# 6_uart_esc_i2c.net
KiCad netlist of a schematic drawn in Altium Designer
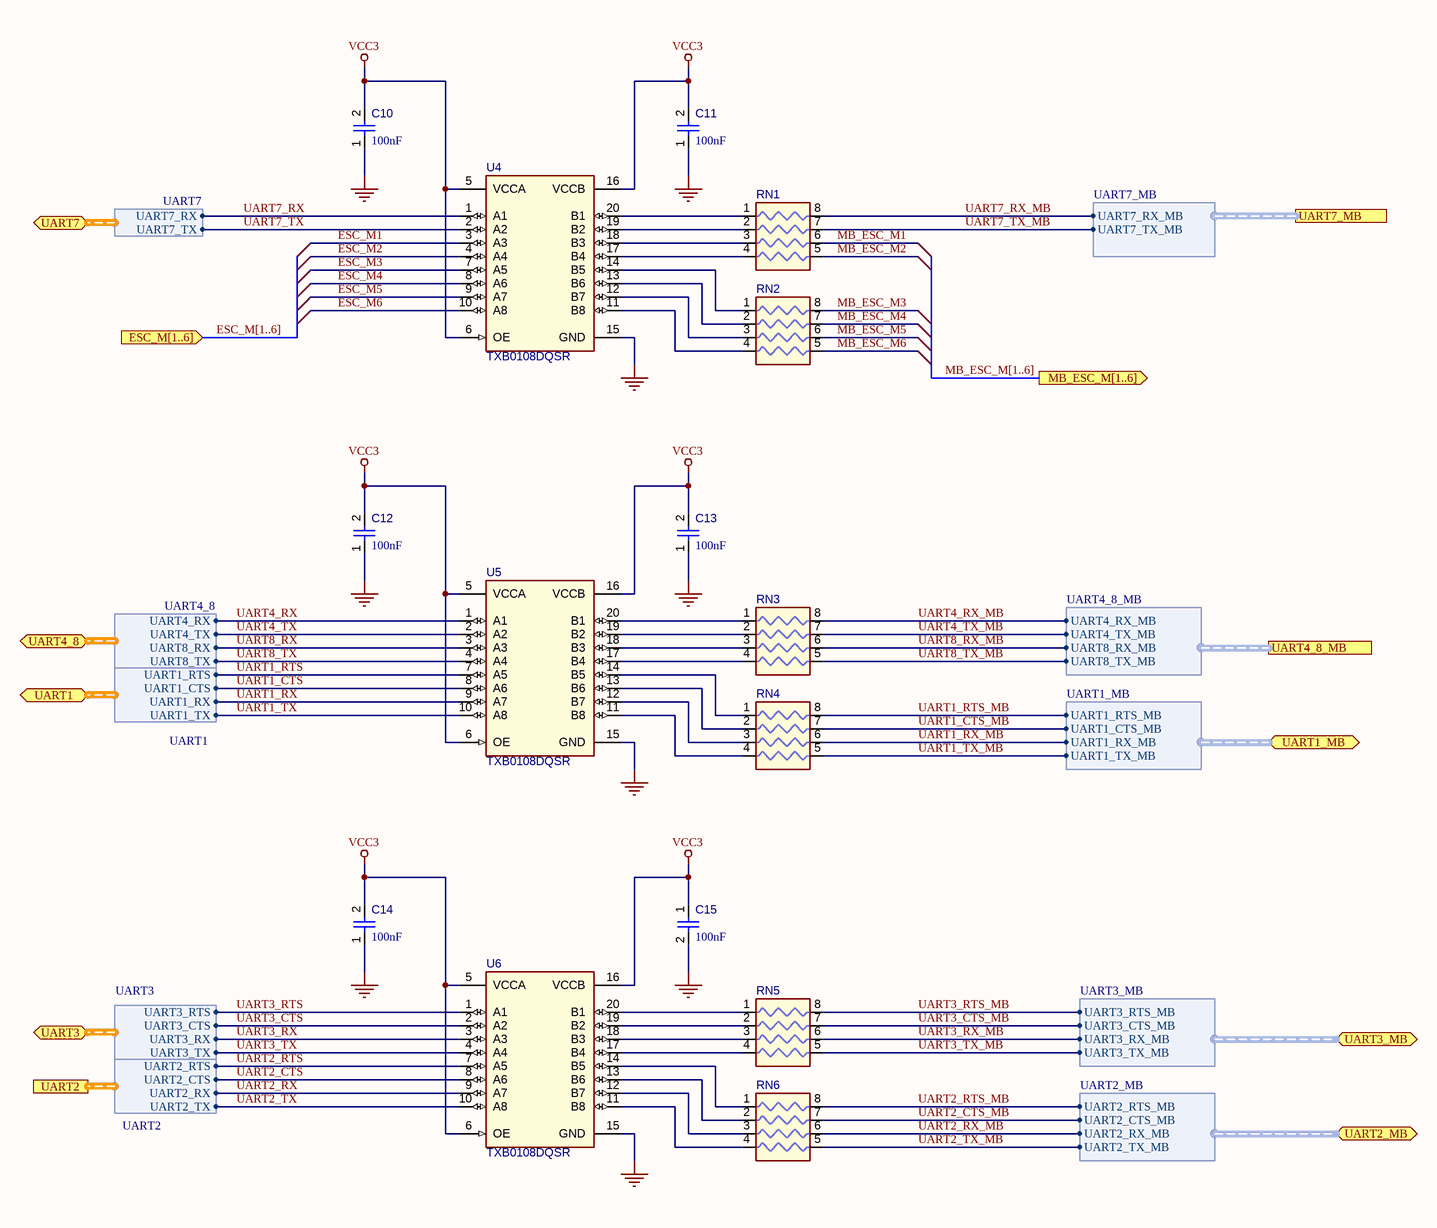
[diagram p0:  6_uart_esc_i2c.SchDoc]

(export (version "E")
  (design (tool "Eeschema 10.0.6"))
  (components
    (comp (ref "C10")
      (value "100nF")
      (footprint "CAPC0402(1005)60_L")
      (description "Chip Capacitor, 100nF +/-20%, 10V, 0402, Thickness 0.6 mm")
      (fields (field (name "TOLERANCE") "20%") (field (name "Comment") "Capacitor 100nF +/-20% 10V 0402"))
      (libsource (lib "MHH -  Altium Advanced Course A365 01") (part "CAP-NP-2"))
    )
    (comp (ref "C11")
      (value "100nF")
      (footprint "CAPC0402(1005)60_L")
      (description "Chip Capacitor, 100nF +/-20%, 10V, 0402, Thickness 0.6 mm")
      (fields (field (name "TOLERANCE") "20%") (field (name "Comment") "Capacitor 100nF +/-20% 10V 0402"))
      (libsource (lib "MHH -  Altium Advanced Course A365 01") (part "CAP-NP-2"))
    )
    (comp (ref "C12")
      (value "100nF")
      (footprint "CAPC0402(1005)60_L")
      (description "Chip Capacitor, 100nF +/-20%, 10V, 0402, Thickness 0.6 mm")
      (fields (field (name "TOLERANCE") "20%") (field (name "Comment") "Capacitor 100nF +/-20% 10V 0402"))
      (libsource (lib "MHH -  Altium Advanced Course A365 01") (part "CAP-NP-2"))
    )
    (comp (ref "C13")
      (value "100nF")
      (footprint "CAPC0402(1005)60_L")
      (description "Chip Capacitor, 100nF +/-20%, 10V, 0402, Thickness 0.6 mm")
      (fields (field (name "TOLERANCE") "20%") (field (name "Comment") "Capacitor 100nF +/-20% 10V 0402"))
      (libsource (lib "MHH -  Altium Advanced Course A365 01") (part "CAP-NP-2"))
    )
    (comp (ref "C14")
      (value "100nF")
      (footprint "CAPC0402(1005)60_L")
      (description "Chip Capacitor, 100nF +/-20%, 10V, 0402, Thickness 0.6 mm")
      (fields (field (name "TOLERANCE") "20%") (field (name "Comment") "Capacitor 100nF +/-20% 10V 0402"))
      (libsource (lib "MHH -  Altium Advanced Course A365 01") (part "CAP-NP-2"))
    )
    (comp (ref "C15")
      (value "100nF")
      (footprint "CAPC0402(1005)60_L")
      (description "Chip Capacitor, 100nF +/-20%, 10V, 0402, Thickness 0.6 mm")
      (fields (field (name "TOLERANCE") "20%") (field (name "Comment") "Capacitor 100nF +/-20% 10V 0402"))
      (libsource (lib "MHH -  Altium Advanced Course A365 01") (part "CAP-NP-2"))
    )
    (comp (ref "RN1")
      (value "Resistor 200R +/-5% 0402 62.5 mW")
      (footprint "Panasonic_EXB28")
      (fields (field (name "TOLERANCE") "5%") (field (name "POWER") "62.5mW"))
      (libsource (lib "MHH -  Altium Advanced Course A365 01") (part "RES-P-4"))
    )
    (comp (ref "RN2")
      (value "Resistor 200R +/-5% 0402 62.5 mW")
      (footprint "Panasonic_EXB28")
      (fields (field (name "TOLERANCE") "5%") (field (name "POWER") "62.5mW"))
      (libsource (lib "MHH -  Altium Advanced Course A365 01") (part "RES-P-4"))
    )
    (comp (ref "RN3")
      (value "Resistor 200R +/-5% 0402 62.5 mW")
      (footprint "Panasonic_EXB28")
      (fields (field (name "TOLERANCE") "5%") (field (name "POWER") "62.5mW"))
      (libsource (lib "MHH -  Altium Advanced Course A365 01") (part "RES-P-4"))
    )
    (comp (ref "RN4")
      (value "Resistor 200R +/-5% 0402 62.5 mW")
      (footprint "Panasonic_EXB28")
      (fields (field (name "TOLERANCE") "5%") (field (name "POWER") "62.5mW"))
      (libsource (lib "MHH -  Altium Advanced Course A365 01") (part "RES-P-4"))
    )
    (comp (ref "RN5")
      (value "Resistor 200R +/-5% 0402 62.5 mW")
      (footprint "Panasonic_EXB28")
      (fields (field (name "TOLERANCE") "5%") (field (name "POWER") "62.5mW"))
      (libsource (lib "MHH -  Altium Advanced Course A365 01") (part "RES-P-4"))
    )
    (comp (ref "RN6")
      (value "Resistor 200R +/-5% 0402 62.5 mW")
      (footprint "Panasonic_EXB28")
      (fields (field (name "TOLERANCE") "5%") (field (name "POWER") "62.5mW"))
      (libsource (lib "MHH -  Altium Advanced Course A365 01") (part "RES-P-4"))
    )
    (comp (ref "U4")
      (value "TXB0108DQSR")
      (footprint "DQS0020A_V")
      (libsource (lib "MHH -  Altium Advanced Course A365 01") (part "CMP-00162-7"))
    )
    (comp (ref "U5")
      (value "TXB0108DQSR")
      (footprint "DQS0020A_V")
      (libsource (lib "MHH -  Altium Advanced Course A365 01") (part "CMP-00162-7"))
    )
    (comp (ref "U6")
      (value "TXB0108DQSR")
      (footprint "DQS0020A_V")
      (libsource (lib "MHH -  Altium Advanced Course A365 01") (part "CMP-00162-7"))
    )
  )
  (nets
    (net (code "11") (name "/ESC_M1") (class "Default")
      (node (ref "U4") (pin "3") (pinfunction "A3_3") (pintype "bidirectional"))
    )
    (net (code "12") (name "/ESC_M2") (class "Default")
      (node (ref "U4") (pin "4") (pinfunction "A4_4") (pintype "bidirectional"))
    )
    (net (code "13") (name "/ESC_M3") (class "Default")
      (node (ref "U4") (pin "7") (pinfunction "A5_7") (pintype "bidirectional"))
    )
    (net (code "14") (name "/ESC_M4") (class "Default")
      (node (ref "U4") (pin "8") (pinfunction "A6_8") (pintype "bidirectional"))
    )
    (net (code "15") (name "/ESC_M5") (class "Default")
      (node (ref "U4") (pin "9") (pinfunction "A7_9") (pintype "bidirectional"))
    )
    (net (code "16") (name "/ESC_M6") (class "Default")
      (node (ref "U4") (pin "10") (pinfunction "A8_10") (pintype "bidirectional"))
    )
    (net (code "18") (name "/MB_ESC_M1") (class "Default")
      (node (ref "RN1") (pin "6") (pinfunction "2_6") (pintype "passive"))
    )
    (net (code "19") (name "/MB_ESC_M2") (class "Default")
      (node (ref "RN1") (pin "5") (pinfunction "2_5") (pintype "passive"))
    )
    (net (code "20") (name "/MB_ESC_M3") (class "Default")
      (node (ref "RN2") (pin "8") (pinfunction "2_8") (pintype "passive"))
    )
    (net (code "21") (name "/MB_ESC_M4") (class "Default")
      (node (ref "RN2") (pin "7") (pinfunction "2_7") (pintype "passive"))
    )
    (net (code "22") (name "/MB_ESC_M5") (class "Default")
      (node (ref "RN2") (pin "6") (pinfunction "2_6") (pintype "passive"))
    )
    (net (code "23") (name "/MB_ESC_M6") (class "Default")
      (node (ref "RN2") (pin "5") (pinfunction "2_5") (pintype "passive"))
    )
    (net (code "25") (name "/UART1_CTS") (class "Default")
      (node (ref "U5") (pin "8") (pinfunction "A6_8") (pintype "bidirectional"))
    )
    (net (code "26") (name "/UART1_CTS_MB") (class "Default")
      (node (ref "RN4") (pin "7") (pinfunction "2_7") (pintype "passive"))
    )
    (net (code "27") (name "/UART1_RTS") (class "Default")
      (node (ref "U5") (pin "7") (pinfunction "A5_7") (pintype "bidirectional"))
    )
    (net (code "28") (name "/UART1_RTS_MB") (class "Default")
      (node (ref "RN4") (pin "8") (pinfunction "2_8") (pintype "passive"))
    )
    (net (code "29") (name "/UART1_RX") (class "Default")
      (node (ref "U5") (pin "9") (pinfunction "A7_9") (pintype "bidirectional"))
    )
    (net (code "30") (name "/UART1_RX_MB") (class "Default")
      (node (ref "RN4") (pin "6") (pinfunction "2_6") (pintype "passive"))
    )
    (net (code "31") (name "/UART1_TX") (class "Default")
      (node (ref "U5") (pin "10") (pinfunction "A8_10") (pintype "bidirectional"))
    )
    (net (code "32") (name "/UART1_TX_MB") (class "Default")
      (node (ref "RN4") (pin "5") (pinfunction "2_5") (pintype "passive"))
    )
    (net (code "33") (name "/UART2_CTS") (class "Default")
      (node (ref "U6") (pin "8") (pinfunction "A6_8") (pintype "bidirectional"))
    )
    (net (code "34") (name "/UART2_CTS_MB") (class "Default")
      (node (ref "RN6") (pin "7") (pinfunction "2_7") (pintype "passive"))
    )
    (net (code "35") (name "/UART2_RTS") (class "Default")
      (node (ref "U6") (pin "7") (pinfunction "A5_7") (pintype "bidirectional"))
    )
    (net (code "36") (name "/UART2_RTS_MB") (class "Default")
      (node (ref "RN6") (pin "8") (pinfunction "2_8") (pintype "passive"))
    )
    (net (code "37") (name "/UART2_RX") (class "Default")
      (node (ref "U6") (pin "9") (pinfunction "A7_9") (pintype "bidirectional"))
    )
    (net (code "38") (name "/UART2_RX_MB") (class "Default")
      (node (ref "RN6") (pin "6") (pinfunction "2_6") (pintype "passive"))
    )
    (net (code "39") (name "/UART2_TX") (class "Default")
      (node (ref "U6") (pin "10") (pinfunction "A8_10") (pintype "bidirectional"))
    )
    (net (code "40") (name "/UART2_TX_MB") (class "Default")
      (node (ref "RN6") (pin "5") (pinfunction "2_5") (pintype "passive"))
    )
    (net (code "41") (name "/UART3_CTS") (class "Default")
      (node (ref "U6") (pin "2") (pinfunction "A2_2") (pintype "bidirectional"))
    )
    (net (code "42") (name "/UART3_CTS_MB") (class "Default")
      (node (ref "RN5") (pin "7") (pinfunction "2_7") (pintype "passive"))
    )
    (net (code "43") (name "/UART3_RTS") (class "Default")
      (node (ref "U6") (pin "1") (pinfunction "A1_1") (pintype "bidirectional"))
    )
    (net (code "44") (name "/UART3_RTS_MB") (class "Default")
      (node (ref "RN5") (pin "8") (pinfunction "2_8") (pintype "passive"))
    )
    (net (code "45") (name "/UART3_RX") (class "Default")
      (node (ref "U6") (pin "3") (pinfunction "A3_3") (pintype "bidirectional"))
    )
    (net (code "46") (name "/UART3_RX_MB") (class "Default")
      (node (ref "RN5") (pin "6") (pinfunction "2_6") (pintype "passive"))
    )
    (net (code "47") (name "/UART3_TX") (class "Default")
      (node (ref "U6") (pin "4") (pinfunction "A4_4") (pintype "bidirectional"))
    )
    (net (code "48") (name "/UART3_TX_MB") (class "Default")
      (node (ref "RN5") (pin "5") (pinfunction "2_5") (pintype "passive"))
    )
    (net (code "49") (name "/UART4_RX") (class "Default")
      (node (ref "U5") (pin "1") (pinfunction "A1_1") (pintype "bidirectional"))
    )
    (net (code "50") (name "/UART4_RX_MB") (class "Default")
      (node (ref "RN3") (pin "8") (pinfunction "2_8") (pintype "passive"))
    )
    (net (code "51") (name "/UART4_TX") (class "Default")
      (node (ref "U5") (pin "2") (pinfunction "A2_2") (pintype "bidirectional"))
    )
    (net (code "52") (name "/UART4_TX_MB") (class "Default")
      (node (ref "RN3") (pin "7") (pinfunction "2_7") (pintype "passive"))
    )
    (net (code "53") (name "/UART7_RX") (class "Default")
      (node (ref "U4") (pin "1") (pinfunction "A1_1") (pintype "bidirectional"))
    )
    (net (code "54") (name "/UART7_RX_MB") (class "Default")
      (node (ref "RN1") (pin "8") (pinfunction "2_8") (pintype "passive"))
    )
    (net (code "55") (name "/UART7_TX") (class "Default")
      (node (ref "U4") (pin "2") (pinfunction "A2_2") (pintype "bidirectional"))
    )
    (net (code "56") (name "/UART7_TX_MB") (class "Default")
      (node (ref "RN1") (pin "7") (pinfunction "2_7") (pintype "passive"))
    )
    (net (code "57") (name "/UART8_RX") (class "Default")
      (node (ref "U5") (pin "3") (pinfunction "A3_3") (pintype "bidirectional"))
    )
    (net (code "58") (name "/UART8_RX_MB") (class "Default")
      (node (ref "RN3") (pin "6") (pinfunction "2_6") (pintype "passive"))
    )
    (net (code "59") (name "/UART8_TX") (class "Default")
      (node (ref "U5") (pin "4") (pinfunction "A4_4") (pintype "bidirectional"))
    )
    (net (code "60") (name "/UART8_TX_MB") (class "Default")
      (node (ref "RN3") (pin "5") (pinfunction "2_5") (pintype "passive"))
    )
    (net (code "71") (name "GND") (class "Default")
      (node (ref "C10") (pin "1") (pinfunction "1_1") (pintype "passive"))
      (node (ref "C11") (pin "1") (pinfunction "1_1") (pintype "passive"))
      (node (ref "C12") (pin "1") (pinfunction "1_1") (pintype "passive"))
      (node (ref "C13") (pin "1") (pinfunction "1_1") (pintype "passive"))
      (node (ref "C14") (pin "1") (pinfunction "1_1") (pintype "passive"))
      (node (ref "C15") (pin "2") (pinfunction "2_2") (pintype "passive"))
      (node (ref "U4") (pin "15") (pinfunction "GND_15") (pintype "power_in"))
      (node (ref "U5") (pin "15") (pinfunction "GND_15") (pintype "power_in"))
      (node (ref "U6") (pin "15") (pinfunction "GND_15") (pintype "power_in"))
    )
    (net (code "72") (name "Net-(U4-B1)") (class "Default")
      (node (ref "RN1") (pin "1") (pinfunction "1_1") (pintype "passive"))
      (node (ref "U4") (pin "20") (pinfunction "B1_20") (pintype "bidirectional"))
    )
    (net (code "73") (name "Net-(U4-B2)") (class "Default")
      (node (ref "RN1") (pin "2") (pinfunction "1_2") (pintype "passive"))
      (node (ref "U4") (pin "19") (pinfunction "B2_19") (pintype "bidirectional"))
    )
    (net (code "74") (name "Net-(U4-B3)") (class "Default")
      (node (ref "RN1") (pin "3") (pinfunction "1_3") (pintype "passive"))
      (node (ref "U4") (pin "18") (pinfunction "B3_18") (pintype "bidirectional"))
    )
    (net (code "75") (name "Net-(U4-B4)") (class "Default")
      (node (ref "RN1") (pin "4") (pinfunction "1_4") (pintype "passive"))
      (node (ref "U4") (pin "17") (pinfunction "B4_17") (pintype "bidirectional"))
    )
    (net (code "76") (name "Net-(U4-B5)") (class "Default")
      (node (ref "RN2") (pin "1") (pinfunction "1_1") (pintype "passive"))
      (node (ref "U4") (pin "14") (pinfunction "B5_14") (pintype "bidirectional"))
    )
    (net (code "77") (name "Net-(U4-B6)") (class "Default")
      (node (ref "RN2") (pin "2") (pinfunction "1_2") (pintype "passive"))
      (node (ref "U4") (pin "13") (pinfunction "B6_13") (pintype "bidirectional"))
    )
    (net (code "78") (name "Net-(U4-B7)") (class "Default")
      (node (ref "RN2") (pin "3") (pinfunction "1_3") (pintype "passive"))
      (node (ref "U4") (pin "12") (pinfunction "B7_12") (pintype "bidirectional"))
    )
    (net (code "79") (name "Net-(U4-B8)") (class "Default")
      (node (ref "RN2") (pin "4") (pinfunction "1_4") (pintype "passive"))
      (node (ref "U4") (pin "11") (pinfunction "B8_11") (pintype "bidirectional"))
    )
    (net (code "80") (name "Net-(U5-B1)") (class "Default")
      (node (ref "RN3") (pin "1") (pinfunction "1_1") (pintype "passive"))
      (node (ref "U5") (pin "20") (pinfunction "B1_20") (pintype "bidirectional"))
    )
    (net (code "81") (name "Net-(U5-B2)") (class "Default")
      (node (ref "RN3") (pin "2") (pinfunction "1_2") (pintype "passive"))
      (node (ref "U5") (pin "19") (pinfunction "B2_19") (pintype "bidirectional"))
    )
    (net (code "82") (name "Net-(U5-B3)") (class "Default")
      (node (ref "RN3") (pin "3") (pinfunction "1_3") (pintype "passive"))
      (node (ref "U5") (pin "18") (pinfunction "B3_18") (pintype "bidirectional"))
    )
    (net (code "83") (name "Net-(U5-B4)") (class "Default")
      (node (ref "RN3") (pin "4") (pinfunction "1_4") (pintype "passive"))
      (node (ref "U5") (pin "17") (pinfunction "B4_17") (pintype "bidirectional"))
    )
    (net (code "84") (name "Net-(U5-B5)") (class "Default")
      (node (ref "RN4") (pin "1") (pinfunction "1_1") (pintype "passive"))
      (node (ref "U5") (pin "14") (pinfunction "B5_14") (pintype "bidirectional"))
    )
    (net (code "85") (name "Net-(U5-B6)") (class "Default")
      (node (ref "RN4") (pin "2") (pinfunction "1_2") (pintype "passive"))
      (node (ref "U5") (pin "13") (pinfunction "B6_13") (pintype "bidirectional"))
    )
    (net (code "86") (name "Net-(U5-B7)") (class "Default")
      (node (ref "RN4") (pin "3") (pinfunction "1_3") (pintype "passive"))
      (node (ref "U5") (pin "12") (pinfunction "B7_12") (pintype "bidirectional"))
    )
    (net (code "87") (name "Net-(U5-B8)") (class "Default")
      (node (ref "RN4") (pin "4") (pinfunction "1_4") (pintype "passive"))
      (node (ref "U5") (pin "11") (pinfunction "B8_11") (pintype "bidirectional"))
    )
    (net (code "88") (name "Net-(U6-B1)") (class "Default")
      (node (ref "RN5") (pin "1") (pinfunction "1_1") (pintype "passive"))
      (node (ref "U6") (pin "20") (pinfunction "B1_20") (pintype "bidirectional"))
    )
    (net (code "89") (name "Net-(U6-B2)") (class "Default")
      (node (ref "RN5") (pin "2") (pinfunction "1_2") (pintype "passive"))
      (node (ref "U6") (pin "19") (pinfunction "B2_19") (pintype "bidirectional"))
    )
    (net (code "90") (name "Net-(U6-B3)") (class "Default")
      (node (ref "RN5") (pin "3") (pinfunction "1_3") (pintype "passive"))
      (node (ref "U6") (pin "18") (pinfunction "B3_18") (pintype "bidirectional"))
    )
    (net (code "91") (name "Net-(U6-B4)") (class "Default")
      (node (ref "RN5") (pin "4") (pinfunction "1_4") (pintype "passive"))
      (node (ref "U6") (pin "17") (pinfunction "B4_17") (pintype "bidirectional"))
    )
    (net (code "92") (name "Net-(U6-B5)") (class "Default")
      (node (ref "RN6") (pin "1") (pinfunction "1_1") (pintype "passive"))
      (node (ref "U6") (pin "14") (pinfunction "B5_14") (pintype "bidirectional"))
    )
    (net (code "93") (name "Net-(U6-B6)") (class "Default")
      (node (ref "RN6") (pin "2") (pinfunction "1_2") (pintype "passive"))
      (node (ref "U6") (pin "13") (pinfunction "B6_13") (pintype "bidirectional"))
    )
    (net (code "94") (name "Net-(U6-B7)") (class "Default")
      (node (ref "RN6") (pin "3") (pinfunction "1_3") (pintype "passive"))
      (node (ref "U6") (pin "12") (pinfunction "B7_12") (pintype "bidirectional"))
    )
    (net (code "95") (name "Net-(U6-B8)") (class "Default")
      (node (ref "RN6") (pin "4") (pinfunction "1_4") (pintype "passive"))
      (node (ref "U6") (pin "11") (pinfunction "B8_11") (pintype "bidirectional"))
    )
    (net (code "96") (name "VCC3") (class "Default")
      (node (ref "C10") (pin "2") (pinfunction "2_2") (pintype "passive"))
      (node (ref "C11") (pin "2") (pinfunction "2_2") (pintype "passive"))
      (node (ref "C12") (pin "2") (pinfunction "2_2") (pintype "passive"))
      (node (ref "C13") (pin "2") (pinfunction "2_2") (pintype "passive"))
      (node (ref "C14") (pin "2") (pinfunction "2_2") (pintype "passive"))
      (node (ref "C15") (pin "1") (pinfunction "1_1") (pintype "passive"))
      (node (ref "U4") (pin "16") (pinfunction "VCCB_16") (pintype "power_in"))
      (node (ref "U4") (pin "5") (pinfunction "VCCA_5") (pintype "power_in"))
      (node (ref "U4") (pin "6") (pinfunction "OE_6") (pintype "input"))
      (node (ref "U5") (pin "16") (pinfunction "VCCB_16") (pintype "power_in"))
      (node (ref "U5") (pin "5") (pinfunction "VCCA_5") (pintype "power_in"))
      (node (ref "U5") (pin "6") (pinfunction "OE_6") (pintype "input"))
      (node (ref "U6") (pin "16") (pinfunction "VCCB_16") (pintype "power_in"))
      (node (ref "U6") (pin "5") (pinfunction "VCCA_5") (pintype "power_in"))
      (node (ref "U6") (pin "6") (pinfunction "OE_6") (pintype "input"))
    )
  )
)
